# TRISECT_Leg.net
KiCad netlist of a schematic drawn in Altium Designer
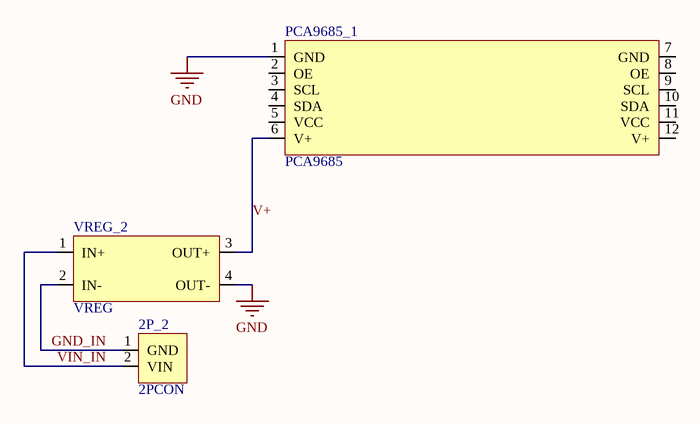
[diagram p0: TRISECT_Leg.SchDoc]

(export (version "E")
  (design (tool "Eeschema 10.0.6"))
  (components
    (comp (ref "2P_2")
      (value "2PCON")
      (footprint "2PCON")
      (description "2 pin connector")
      (libsource (lib "TRISECT_Custom") (part "2PCON"))
    )
    (comp (ref "PCA9685_1")
      (value "PCA9685")
      (footprint "PCA9685")
      (description "PCA9685 PWM Servo Driver")
      (libsource (lib "TRISECT_Custom") (part "PCA9685"))
    )
    (comp (ref "VREG_2")
      (value "VREG")
      (footprint "VREG")
      (description "Voltage Regulator - basic pinout")
      (libsource (lib "TRISECT_Custom") (part "VREG"))
    )
  )
  (nets
    (net (code "1") (name "/GND_IN") (class "Default")
      (node (ref "2P_2") (pin "1") (pinfunction "GND_1") (pintype "passive"))
      (node (ref "VREG_2") (pin "2") (pinfunction "IN-_2") (pintype "passive"))
    )
    (net (code "2") (name "/V+") (class "Default")
      (node (ref "PCA9685_1") (pin "6") (pinfunction "V+_6") (pintype "passive"))
      (node (ref "VREG_2") (pin "3") (pinfunction "OUT+_3") (pintype "passive"))
    )
    (net (code "3") (name "/VIN_IN") (class "Default")
      (node (ref "2P_2") (pin "2") (pinfunction "VIN_2") (pintype "passive"))
      (node (ref "VREG_2") (pin "1") (pinfunction "IN+_1") (pintype "passive"))
    )
    (net (code "4") (name "GND") (class "Default")
      (node (ref "PCA9685_1") (pin "1") (pinfunction "GND_1") (pintype "passive"))
      (node (ref "VREG_2") (pin "4") (pinfunction "OUT-_4") (pintype "passive"))
    )
    (net (code "5") (name "unconnected-(PCA9685_1-GND-Pad7)") (class "Default")
      (node (ref "PCA9685_1") (pin "7") (pinfunction "GND_7") (pintype "passive"))
    )
    (net (code "6") (name "unconnected-(PCA9685_1-OE-Pad2)") (class "Default")
      (node (ref "PCA9685_1") (pin "2") (pinfunction "OE_2") (pintype "passive"))
    )
    (net (code "7") (name "unconnected-(PCA9685_1-OE-Pad8)") (class "Default")
      (node (ref "PCA9685_1") (pin "8") (pinfunction "OE_8") (pintype "passive"))
    )
    (net (code "8") (name "unconnected-(PCA9685_1-SCL-Pad3)") (class "Default")
      (node (ref "PCA9685_1") (pin "3") (pinfunction "SCL_3") (pintype "passive"))
    )
    (net (code "9") (name "unconnected-(PCA9685_1-SCL-Pad9)") (class "Default")
      (node (ref "PCA9685_1") (pin "9") (pinfunction "SCL_9") (pintype "passive"))
    )
    (net (code "10") (name "unconnected-(PCA9685_1-SDA-Pad4)") (class "Default")
      (node (ref "PCA9685_1") (pin "4") (pinfunction "SDA_4") (pintype "passive"))
    )
    (net (code "11") (name "unconnected-(PCA9685_1-SDA-Pad10)") (class "Default")
      (node (ref "PCA9685_1") (pin "10") (pinfunction "SDA_10") (pintype "passive"))
    )
    (net (code "12") (name "unconnected-(PCA9685_1-V+-Pad12)") (class "Default")
      (node (ref "PCA9685_1") (pin "12") (pinfunction "V+_12") (pintype "passive"))
    )
    (net (code "13") (name "unconnected-(PCA9685_1-VCC-Pad5)") (class "Default")
      (node (ref "PCA9685_1") (pin "5") (pinfunction "VCC_5") (pintype "passive"))
    )
    (net (code "14") (name "unconnected-(PCA9685_1-VCC-Pad11)") (class "Default")
      (node (ref "PCA9685_1") (pin "11") (pinfunction "VCC_11") (pintype "passive"))
    )
  )
)
